# 5_0inch_IPS_for_TerasicDEs.net
KiCad netlist of a schematic drawn in Altium Designer
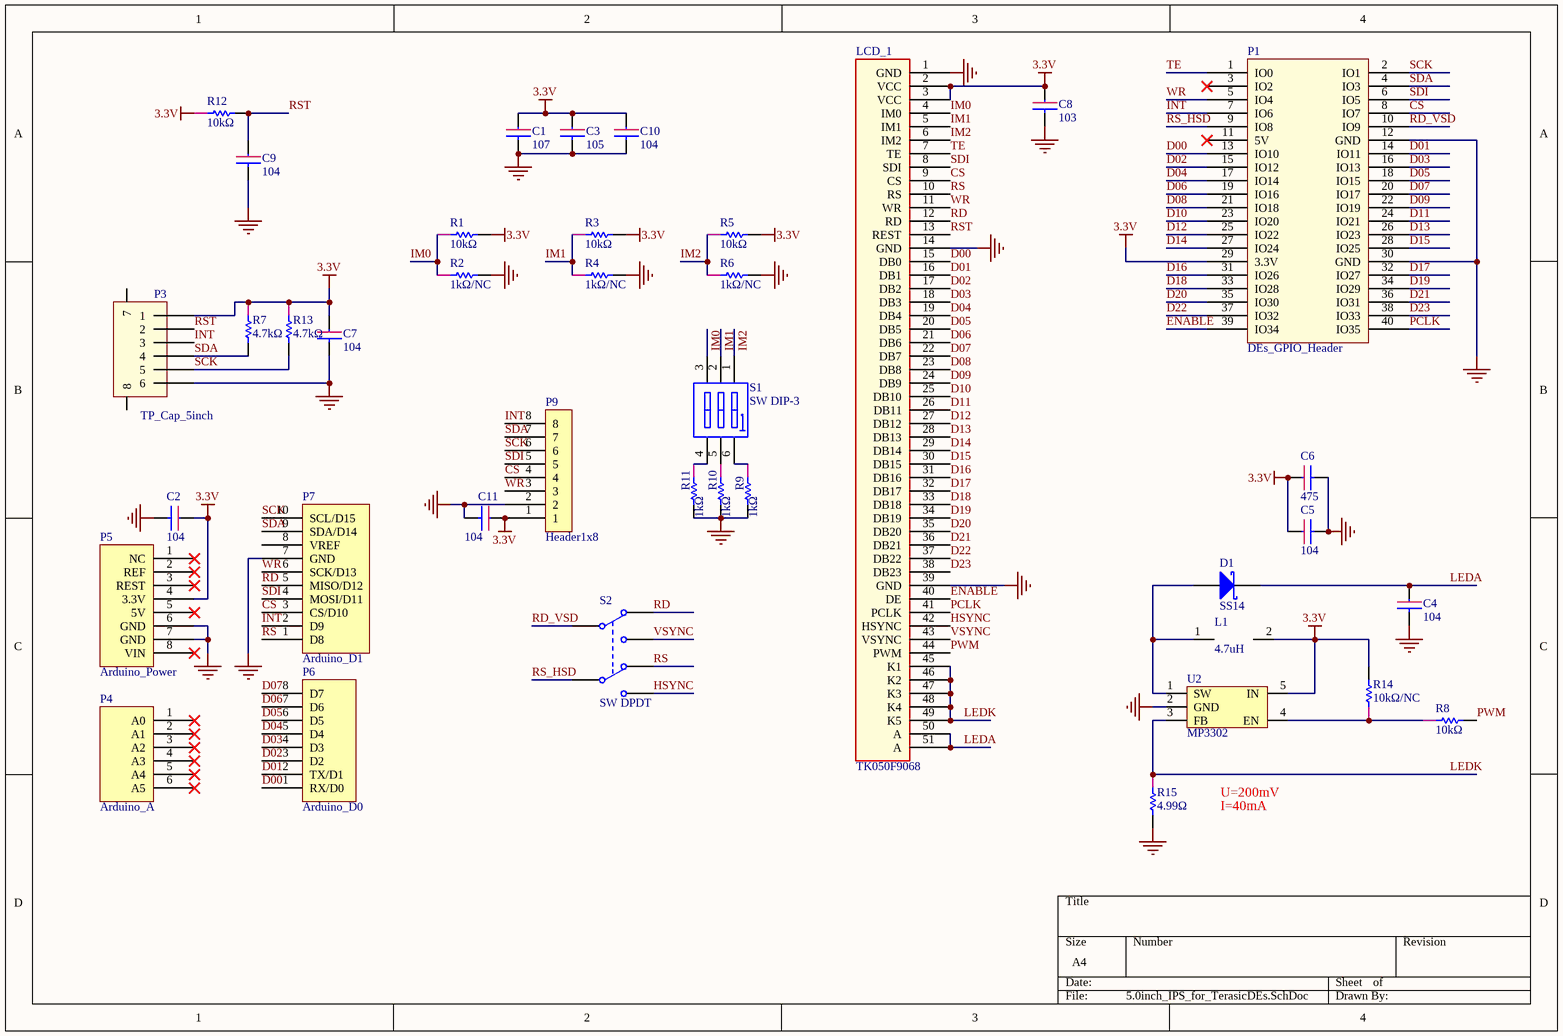
[diagram p0: 5.0inch_IPS_for_TerasicDEs.SchDoc]

(export (version "E")
  (design (tool "Eeschema 10.0.6"))
  (components
    (comp (ref "C1") (value "107") (footprint "C3528B") (libsource (lib "Tiky") (part "cap")))
    (comp (ref "C2") (value "104") (footprint "C0603-2") (libsource (lib "Tiky") (part "cap")))
    (comp (ref "C3") (value "105") (footprint "C3216A") (libsource (lib "Tiky") (part "cap")))
    (comp (ref "C4") (value "104") (footprint "C0603-2") (libsource (lib "Tiky") (part "cap")))
    (comp (ref "C5") (value "104") (footprint "C0603-1") (libsource (lib "Tiky") (part "cap")))
    (comp (ref "C6") (value "475") (footprint "C0603-2") (libsource (lib "Tiky") (part "cap")))
    (comp (ref "C7") (value "104") (footprint "C0603-1") (libsource (lib "Tiky") (part "cap")))
    (comp (ref "C8") (value "103") (footprint "C0603-1") (libsource (lib "Tiky") (part "cap")))
    (comp (ref "C9")
      (value "104")
      (footprint "C0603-2")
      (libsource (lib "5.0inch_IPS_for_TerasicDEs") (part "cap"))
    )
    (comp (ref "C10") (value "104") (footprint "C0603-1") (libsource (lib "Tiky") (part "cap")))
    (comp (ref "C11") (value "104") (footprint "C0603-2") (libsource (lib "Tiky") (part "cap")))
    (comp (ref "D1")
      (value "SS14")
      (footprint "SOD123")
      (description "Schottky Diode")
      (fields (field (name "PUBLISHER") "Altium Limited"))
      (libsource (lib "Miscellaneous Devices") (part "D Schottky"))
    )
    (comp (ref "L1") (value "4.7uH") (footprint "L453226") (libsource (lib "Tiky") (part "Inductor")))
    (comp (ref "LCD_1")
      (value "TK050F9068")
      (footprint "TK050F5590")
      (libsource (lib "Tiky") (part "TK050F9068"))
    )
    (comp (ref "P1")
      (value "DEs_GPIO_Header")
      (footprint "P_HEAD_2X20-n")
      (libsource (lib "5.0inch_IPS_for_TerasicDEs") (part "DEs_GPIO_Header"))
    )
    (comp (ref "P3")
      (value "TP_Cap_5inch")
      (footprint "TP_CAP_5INCH")
      (libsource (lib "Tiky") (part "BHEADSMD1x6"))
    )
    (comp (ref "P4")
      (value "Arduino_A")
      (footprint "SMT_Pin1x6C")
      (libsource (lib "5.0_inch_IPS_TFT_for_Terasic_DE_Boards") (part "Arduino_A"))
    )
    (comp (ref "P5")
      (value "Arduino_Power")
      (footprint "SMT_Pin1x8C")
      (libsource (lib "5.0_inch_IPS_TFT_for_Terasic_DE_Boards") (part "Arduino_Power"))
    )
    (comp (ref "P6")
      (value "Arduino_D0")
      (footprint "SMT_Pin1x8C")
      (libsource (lib "5.0_inch_IPS_TFT_for_Terasic_DE_Boards") (part "Arduino_D0"))
    )
    (comp (ref "P7")
      (value "Arduino_D1")
      (footprint "SMT_Pin1x10C")
      (libsource (lib "5.0_inch_IPS_TFT_for_Terasic_DE_Boards") (part "Arduino_D1"))
    )
    (comp (ref "P9")
      (value "Header1x8")
      (footprint "SMT_Pin1x8")
      (libsource (lib "5.0inch_IPS_for_TerasicDEs") (part "Header1x8"))
    )
    (comp (ref "R1") (value "10kΩ") (footprint "R0603") (libsource (lib "Tiky") (part "Resistor")))
    (comp (ref "R2") (value "1kΩ/NC") (footprint "R0603") (libsource (lib "Tiky") (part "Resistor")))
    (comp (ref "R3") (value "10kΩ") (footprint "R0603") (libsource (lib "Tiky") (part "Resistor")))
    (comp (ref "R4") (value "1kΩ/NC") (footprint "R0603") (libsource (lib "Tiky") (part "Resistor")))
    (comp (ref "R5") (value "10kΩ") (footprint "R0603") (libsource (lib "Tiky") (part "Resistor")))
    (comp (ref "R6") (value "1kΩ/NC") (footprint "R0603") (libsource (lib "Tiky") (part "Resistor")))
    (comp (ref "R7") (value "4.7kΩ") (footprint "R0603") (libsource (lib "Tiky") (part "Resistor")))
    (comp (ref "R8") (value "10kΩ") (footprint "R0603") (libsource (lib "Tiky") (part "Resistor")))
    (comp (ref "R9")
      (value "1kΩ")
      (footprint "R0603")
      (libsource (lib "5.0inch_IPS_for_TerasicDEs") (part "Resistor"))
    )
    (comp (ref "R10")
      (value "1kΩ")
      (footprint "R0603")
      (libsource (lib "5.0inch_IPS_for_TerasicDEs") (part "Resistor"))
    )
    (comp (ref "R11")
      (value "1kΩ")
      (footprint "R0603")
      (libsource (lib "5.0inch_IPS_for_TerasicDEs") (part "Resistor"))
    )
    (comp (ref "R12")
      (value "10kΩ")
      (footprint "R0603")
      (libsource (lib "5.0inch_IPS_for_TerasicDEs") (part "Resistor"))
    )
    (comp (ref "R13")
      (value "4.7kΩ")
      (footprint "R0603")
      (libsource (lib "5.0inch_IPS_for_TerasicDEs") (part "Resistor"))
    )
    (comp (ref "R14") (value "10kΩ/NC") (footprint "R0603") (libsource (lib "Tiky") (part "Resistor")))
    (comp (ref "R15") (value "4.99Ω") (footprint "R0603") (libsource (lib "Tiky") (part "Resistor")))
    (comp (ref "S1")
      (value "SW DIP-3")
      (footprint "DIP3-1.27")
      (description "DIP Switch, 3 Position, SPST")
      (fields (field (name "PUBLISHER") "Altium Limited"))
      (libsource (lib "Miscellaneous Devices") (part "SW DIP-3"))
    )
    (comp (ref "S2")
      (value "SW DPDT")
      (footprint "MSS-22C02")
      (description "Switch")
      (fields (field (name "PUBLISHER") "Altium Limited"))
      (libsource (lib "5.0inch_IPS_for_TerasicDEs") (part "SW DPDT"))
    )
    (comp (ref "U2") (value "MP3302") (footprint "SOT23-5") (libsource (lib "Tiky") (part "MP3302")))
  )
  (nets
    (net (code "1") (name "/CS") (class "Default")
      (node (ref "LCD_1") (pin "9") (pinfunction "CS_9") (pintype "passive"))
      (node (ref "P1") (pin "8") (pinfunction "IO7_8") (pintype "passive"))
      (node (ref "P7") (pin "3") (pinfunction "CS/D10_3") (pintype "passive"))
      (node (ref "P9") (pin "4") (pinfunction "4_4") (pintype "passive"))
    )
    (net (code "2") (name "/D00") (class "Default")
      (node (ref "LCD_1") (pin "15") (pinfunction "DB0_15") (pintype "passive"))
      (node (ref "P1") (pin "13") (pinfunction "IO10_13") (pintype "passive"))
      (node (ref "P6") (pin "1") (pinfunction "RX/D0_1") (pintype "passive"))
    )
    (net (code "3") (name "/D01") (class "Default")
      (node (ref "LCD_1") (pin "16") (pinfunction "DB1_16") (pintype "passive"))
      (node (ref "P1") (pin "14") (pinfunction "IO11_14") (pintype "passive"))
      (node (ref "P6") (pin "2") (pinfunction "TX/D1_2") (pintype "passive"))
    )
    (net (code "4") (name "/D02") (class "Default")
      (node (ref "LCD_1") (pin "17") (pinfunction "DB2_17") (pintype "passive"))
      (node (ref "P1") (pin "15") (pinfunction "IO12_15") (pintype "passive"))
      (node (ref "P6") (pin "3") (pinfunction "D2_3") (pintype "passive"))
    )
    (net (code "5") (name "/D03") (class "Default")
      (node (ref "LCD_1") (pin "18") (pinfunction "DB3_18") (pintype "passive"))
      (node (ref "P1") (pin "16") (pinfunction "IO13_16") (pintype "passive"))
      (node (ref "P6") (pin "4") (pinfunction "D3_4") (pintype "passive"))
    )
    (net (code "6") (name "/D04") (class "Default")
      (node (ref "LCD_1") (pin "19") (pinfunction "DB4_19") (pintype "passive"))
      (node (ref "P1") (pin "17") (pinfunction "IO14_17") (pintype "passive"))
      (node (ref "P6") (pin "5") (pinfunction "D4_5") (pintype "passive"))
    )
    (net (code "7") (name "/D05") (class "Default")
      (node (ref "LCD_1") (pin "20") (pinfunction "DB5_20") (pintype "passive"))
      (node (ref "P1") (pin "18") (pinfunction "IO15_18") (pintype "passive"))
      (node (ref "P6") (pin "6") (pinfunction "D5_6") (pintype "passive"))
    )
    (net (code "8") (name "/D06") (class "Default")
      (node (ref "LCD_1") (pin "21") (pinfunction "DB6_21") (pintype "passive"))
      (node (ref "P1") (pin "19") (pinfunction "IO16_19") (pintype "passive"))
      (node (ref "P6") (pin "7") (pinfunction "D6_7") (pintype "passive"))
    )
    (net (code "9") (name "/D07") (class "Default")
      (node (ref "LCD_1") (pin "22") (pinfunction "DB7_22") (pintype "passive"))
      (node (ref "P1") (pin "20") (pinfunction "IO17_20") (pintype "passive"))
      (node (ref "P6") (pin "8") (pinfunction "D7_8") (pintype "passive"))
    )
    (net (code "10") (name "/D08") (class "Default")
      (node (ref "LCD_1") (pin "23") (pinfunction "DB8_23") (pintype "passive"))
      (node (ref "P1") (pin "21") (pinfunction "IO18_21") (pintype "passive"))
    )
    (net (code "11") (name "/D09") (class "Default")
      (node (ref "LCD_1") (pin "24") (pinfunction "DB9_24") (pintype "passive"))
      (node (ref "P1") (pin "22") (pinfunction "IO19_22") (pintype "passive"))
    )
    (net (code "12") (name "/D10") (class "Default")
      (node (ref "LCD_1") (pin "25") (pinfunction "DB10_25") (pintype "passive"))
      (node (ref "P1") (pin "23") (pinfunction "IO20_23") (pintype "passive"))
    )
    (net (code "13") (name "/D11") (class "Default")
      (node (ref "LCD_1") (pin "26") (pinfunction "DB11_26") (pintype "passive"))
      (node (ref "P1") (pin "24") (pinfunction "IO21_24") (pintype "passive"))
    )
    (net (code "14") (name "/D12") (class "Default")
      (node (ref "LCD_1") (pin "27") (pinfunction "DB12_27") (pintype "passive"))
      (node (ref "P1") (pin "25") (pinfunction "IO22_25") (pintype "passive"))
    )
    (net (code "15") (name "/D13") (class "Default")
      (node (ref "LCD_1") (pin "28") (pinfunction "DB13_28") (pintype "passive"))
      (node (ref "P1") (pin "26") (pinfunction "IO23_26") (pintype "passive"))
    )
    (net (code "16") (name "/D14") (class "Default")
      (node (ref "LCD_1") (pin "29") (pinfunction "DB14_29") (pintype "passive"))
      (node (ref "P1") (pin "27") (pinfunction "IO24_27") (pintype "passive"))
    )
    (net (code "17") (name "/D15") (class "Default")
      (node (ref "LCD_1") (pin "30") (pinfunction "DB15_30") (pintype "passive"))
      (node (ref "P1") (pin "28") (pinfunction "IO25_28") (pintype "passive"))
    )
    (net (code "18") (name "/D16") (class "Default")
      (node (ref "LCD_1") (pin "31") (pinfunction "DB16_31") (pintype "passive"))
      (node (ref "P1") (pin "31") (pinfunction "IO26_31") (pintype "passive"))
    )
    (net (code "19") (name "/D17") (class "Default")
      (node (ref "LCD_1") (pin "32") (pinfunction "DB17_32") (pintype "passive"))
      (node (ref "P1") (pin "32") (pinfunction "IO27_32") (pintype "passive"))
    )
    (net (code "20") (name "/D18") (class "Default")
      (node (ref "LCD_1") (pin "33") (pinfunction "DB18_33") (pintype "passive"))
      (node (ref "P1") (pin "33") (pinfunction "IO28_33") (pintype "passive"))
    )
    (net (code "21") (name "/D19") (class "Default")
      (node (ref "LCD_1") (pin "34") (pinfunction "DB19_34") (pintype "passive"))
      (node (ref "P1") (pin "34") (pinfunction "IO29_34") (pintype "passive"))
    )
    (net (code "22") (name "/D20") (class "Default")
      (node (ref "LCD_1") (pin "35") (pinfunction "DB20_35") (pintype "passive"))
      (node (ref "P1") (pin "35") (pinfunction "IO30_35") (pintype "passive"))
    )
    (net (code "23") (name "/D21") (class "Default")
      (node (ref "LCD_1") (pin "36") (pinfunction "DB21_36") (pintype "passive"))
      (node (ref "P1") (pin "36") (pinfunction "IO31_36") (pintype "passive"))
    )
    (net (code "24") (name "/D22") (class "Default")
      (node (ref "LCD_1") (pin "37") (pinfunction "DB22_37") (pintype "passive"))
      (node (ref "P1") (pin "37") (pinfunction "IO32_37") (pintype "passive"))
    )
    (net (code "25") (name "/D23") (class "Default")
      (node (ref "LCD_1") (pin "38") (pinfunction "DB23_38") (pintype "passive"))
      (node (ref "P1") (pin "38") (pinfunction "IO33_38") (pintype "passive"))
    )
    (net (code "26") (name "/ENABLE") (class "Default")
      (node (ref "LCD_1") (pin "40") (pinfunction "DE_40") (pintype "passive"))
      (node (ref "P1") (pin "39") (pinfunction "IO34_39") (pintype "passive"))
    )
    (net (code "27") (name "/HSYNC") (class "Default")
      (node (ref "LCD_1") (pin "42") (pinfunction "HSYNC_42") (pintype "passive"))
      (node (ref "S2") (pin "4") (pinfunction "NO2_4") (pintype "passive"))
    )
    (net (code "28") (name "/IM0") (class "Default")
      (node (ref "LCD_1") (pin "4") (pinfunction "IM0_4") (pintype "passive"))
      (node (ref "R1") (pin "1") (pinfunction "1_1") (pintype "passive"))
      (node (ref "R2") (pin "1") (pinfunction "1_1") (pintype "passive"))
      (node (ref "S1") (pin "3") (pinfunction "A3_3") (pintype "passive"))
    )
    (net (code "29") (name "/IM1") (class "Default")
      (node (ref "LCD_1") (pin "5") (pinfunction "IM1_5") (pintype "passive"))
      (node (ref "R3") (pin "1") (pinfunction "1_1") (pintype "passive"))
      (node (ref "R4") (pin "1") (pinfunction "1_1") (pintype "passive"))
      (node (ref "S1") (pin "2") (pinfunction "A2_2") (pintype "passive"))
    )
    (net (code "30") (name "/IM2") (class "Default")
      (node (ref "LCD_1") (pin "6") (pinfunction "IM2_6") (pintype "passive"))
      (node (ref "R5") (pin "1") (pinfunction "1_1") (pintype "passive"))
      (node (ref "R6") (pin "1") (pinfunction "1_1") (pintype "passive"))
      (node (ref "S1") (pin "1") (pinfunction "A1_1") (pintype "passive"))
    )
    (net (code "31") (name "/INT") (class "Default")
      (node (ref "P1") (pin "7") (pinfunction "IO6_7") (pintype "passive"))
      (node (ref "P3") (pin "3") (pinfunction "3_3") (pintype "passive"))
      (node (ref "P7") (pin "2") (pinfunction "D9_2") (pintype "passive"))
      (node (ref "P9") (pin "8") (pinfunction "8_8") (pintype "passive"))
    )
    (net (code "32") (name "/LEDA") (class "Default")
      (node (ref "C4") (pin "1") (pinfunction "1_1") (pintype "passive"))
      (node (ref "D1") (pin "2") (pinfunction "K_2") (pintype "passive"))
      (node (ref "LCD_1") (pin "50") (pinfunction "A_50") (pintype "passive"))
      (node (ref "LCD_1") (pin "51") (pinfunction "A_51") (pintype "passive"))
    )
    (net (code "33") (name "/LEDK") (class "Default")
      (node (ref "LCD_1") (pin "45") (pinfunction "K1_45") (pintype "passive"))
      (node (ref "LCD_1") (pin "46") (pinfunction "K2_46") (pintype "passive"))
      (node (ref "LCD_1") (pin "47") (pinfunction "K3_47") (pintype "passive"))
      (node (ref "LCD_1") (pin "48") (pinfunction "K4_48") (pintype "passive"))
      (node (ref "LCD_1") (pin "49") (pinfunction "K5_49") (pintype "passive"))
      (node (ref "R15") (pin "1") (pinfunction "1_1") (pintype "passive"))
      (node (ref "U2") (pin "3") (pinfunction "FB_3") (pintype "passive"))
    )
    (net (code "34") (name "/PCLK") (class "Default")
      (node (ref "LCD_1") (pin "41") (pinfunction "PCLK_41") (pintype "passive"))
      (node (ref "P1") (pin "40") (pinfunction "IO35_40") (pintype "passive"))
    )
    (net (code "35") (name "/PWM") (class "Default")
      (node (ref "LCD_1") (pin "44") (pinfunction "PWM_44") (pintype "passive"))
      (node (ref "R8") (pin "2") (pinfunction "2_2") (pintype "passive"))
    )
    (net (code "36") (name "/RD") (class "Default")
      (node (ref "LCD_1") (pin "12") (pinfunction "RD_12") (pintype "passive"))
      (node (ref "P7") (pin "5") (pinfunction "MISO/D12_5") (pintype "passive"))
      (node (ref "S2") (pin "1") (pinfunction "NC1_1") (pintype "passive"))
    )
    (net (code "37") (name "/RD_VSD") (class "Default")
      (node (ref "P1") (pin "10") (pinfunction "IO9_10") (pintype "passive"))
      (node (ref "S2") (pin "2") (pinfunction "COMMON1_2") (pintype "passive"))
    )
    (net (code "38") (name "/RS") (class "Default")
      (node (ref "LCD_1") (pin "10") (pinfunction "RS_10") (pintype "passive"))
      (node (ref "P7") (pin "1") (pinfunction "D8_1") (pintype "passive"))
      (node (ref "S2") (pin "6") (pinfunction "NC2_6") (pintype "passive"))
    )
    (net (code "39") (name "/RST") (class "Default")
      (node (ref "C9") (pin "1") (pinfunction "1_1") (pintype "passive"))
      (node (ref "LCD_1") (pin "13") (pinfunction "REST_13") (pintype "passive"))
      (node (ref "P3") (pin "2") (pinfunction "2_2") (pintype "passive"))
      (node (ref "R12") (pin "2") (pinfunction "2_2") (pintype "passive"))
    )
    (net (code "40") (name "/RS_HSD") (class "Default")
      (node (ref "P1") (pin "9") (pinfunction "IO8_9") (pintype "passive"))
      (node (ref "S2") (pin "5") (pinfunction "COMMON2_5") (pintype "passive"))
    )
    (net (code "41") (name "/SCK") (class "Default")
      (node (ref "P1") (pin "2") (pinfunction "IO1_2") (pintype "passive"))
      (node (ref "P3") (pin "5") (pinfunction "5_5") (pintype "passive"))
      (node (ref "P7") (pin "10") (pinfunction "SCL/D15_10") (pintype "passive"))
      (node (ref "P9") (pin "6") (pinfunction "6_6") (pintype "passive"))
      (node (ref "R13") (pin "2") (pinfunction "2_2") (pintype "passive"))
    )
    (net (code "42") (name "/SDA") (class "Default")
      (node (ref "P1") (pin "4") (pinfunction "IO3_4") (pintype "passive"))
      (node (ref "P3") (pin "4") (pinfunction "4_4") (pintype "passive"))
      (node (ref "P7") (pin "9") (pinfunction "SDA/D14_9") (pintype "passive"))
      (node (ref "P9") (pin "7") (pinfunction "7_7") (pintype "passive"))
      (node (ref "R7") (pin "2") (pinfunction "2_2") (pintype "passive"))
    )
    (net (code "43") (name "/SDI") (class "Default")
      (node (ref "LCD_1") (pin "8") (pinfunction "SDI_8") (pintype "passive"))
      (node (ref "P1") (pin "6") (pinfunction "IO5_6") (pintype "passive"))
      (node (ref "P7") (pin "4") (pinfunction "MOSI/D11_4") (pintype "passive"))
      (node (ref "P9") (pin "5") (pinfunction "5_5") (pintype "passive"))
    )
    (net (code "44") (name "/TE") (class "Default")
      (node (ref "LCD_1") (pin "7") (pinfunction "TE_7") (pintype "passive"))
      (node (ref "P1") (pin "1") (pinfunction "IO0_1") (pintype "passive"))
    )
    (net (code "45") (name "/VSYNC") (class "Default")
      (node (ref "LCD_1") (pin "43") (pinfunction "VSYNC_43") (pintype "passive"))
      (node (ref "S2") (pin "3") (pinfunction "NO1_3") (pintype "passive"))
    )
    (net (code "46") (name "/WR") (class "Default")
      (node (ref "LCD_1") (pin "11") (pinfunction "WR_11") (pintype "passive"))
      (node (ref "P1") (pin "5") (pinfunction "IO4_5") (pintype "passive"))
      (node (ref "P7") (pin "6") (pinfunction "SCK/D13_6") (pintype "passive"))
      (node (ref "P9") (pin "3") (pinfunction "3_3") (pintype "passive"))
    )
    (net (code "47") (name "3.3V") (class "Default")
      (node (ref "C1") (pin "1") (pinfunction "1_1") (pintype "passive"))
      (node (ref "C10") (pin "1") (pinfunction "1_1") (pintype "passive"))
      (node (ref "C11") (pin "1") (pinfunction "1_1") (pintype "passive"))
      (node (ref "C2") (pin "1") (pinfunction "1_1") (pintype "passive"))
      (node (ref "C3") (pin "1") (pinfunction "1_1") (pintype "passive"))
      (node (ref "C5") (pin "1") (pinfunction "1_1") (pintype "passive"))
      (node (ref "C6") (pin "1") (pinfunction "1_1") (pintype "passive"))
      (node (ref "C7") (pin "1") (pinfunction "1_1") (pintype "passive"))
      (node (ref "C8") (pin "1") (pinfunction "1_1") (pintype "passive"))
      (node (ref "L1") (pin "2") (pinfunction "2_2") (pintype "passive"))
      (node (ref "LCD_1") (pin "2") (pinfunction "VCC_2") (pintype "passive"))
      (node (ref "LCD_1") (pin "3") (pinfunction "VCC_3") (pintype "passive"))
      (node (ref "P1") (pin "29") (pinfunction "3.3V_29") (pintype "passive"))
      (node (ref "P3") (pin "1") (pinfunction "1_1") (pintype "passive"))
      (node (ref "P5") (pin "4") (pinfunction "3.3V_4") (pintype "passive"))
      (node (ref "P9") (pin "1") (pinfunction "1_1") (pintype "passive"))
      (node (ref "R1") (pin "2") (pinfunction "2_2") (pintype "passive"))
      (node (ref "R12") (pin "1") (pinfunction "1_1") (pintype "passive"))
      (node (ref "R13") (pin "1") (pinfunction "1_1") (pintype "passive"))
      (node (ref "R14") (pin "2") (pinfunction "2_2") (pintype "passive"))
      (node (ref "R3") (pin "2") (pinfunction "2_2") (pintype "passive"))
      (node (ref "R5") (pin "2") (pinfunction "2_2") (pintype "passive"))
      (node (ref "R7") (pin "1") (pinfunction "1_1") (pintype "passive"))
      (node (ref "U2") (pin "5") (pinfunction "IN_5") (pintype "passive"))
    )
    (net (code "48") (name "GND") (class "Default")
      (node (ref "C1") (pin "2") (pinfunction "2_2") (pintype "passive"))
      (node (ref "C10") (pin "2") (pinfunction "2_2") (pintype "passive"))
      (node (ref "C11") (pin "2") (pinfunction "2_2") (pintype "passive"))
      (node (ref "C2") (pin "2") (pinfunction "2_2") (pintype "passive"))
      (node (ref "C3") (pin "2") (pinfunction "2_2") (pintype "passive"))
      (node (ref "C4") (pin "2") (pinfunction "2_2") (pintype "passive"))
      (node (ref "C5") (pin "2") (pinfunction "2_2") (pintype "passive"))
      (node (ref "C6") (pin "2") (pinfunction "2_2") (pintype "passive"))
      (node (ref "C7") (pin "2") (pinfunction "2_2") (pintype "passive"))
      (node (ref "C8") (pin "2") (pinfunction "2_2") (pintype "passive"))
      (node (ref "C9") (pin "2") (pinfunction "2_2") (pintype "passive"))
      (node (ref "LCD_1") (pin "1") (pinfunction "GND_1") (pintype "passive"))
      (node (ref "LCD_1") (pin "14") (pinfunction "GND_14") (pintype "passive"))
      (node (ref "LCD_1") (pin "39") (pinfunction "GND_39") (pintype "passive"))
      (node (ref "P1") (pin "12") (pinfunction "GND_12") (pintype "passive"))
      (node (ref "P1") (pin "30") (pinfunction "GND_30") (pintype "passive"))
      (node (ref "P3") (pin "6") (pinfunction "6_6") (pintype "passive"))
      (node (ref "P5") (pin "6") (pinfunction "GND_6") (pintype "passive"))
      (node (ref "P5") (pin "7") (pinfunction "GND_7") (pintype "passive"))
      (node (ref "P7") (pin "7") (pinfunction "GND_7") (pintype "passive"))
      (node (ref "P9") (pin "2") (pinfunction "2_2") (pintype "passive"))
      (node (ref "R10") (pin "2") (pinfunction "2_2") (pintype "passive"))
      (node (ref "R11") (pin "2") (pinfunction "2_2") (pintype "passive"))
      (node (ref "R15") (pin "2") (pinfunction "2_2") (pintype "passive"))
      (node (ref "R2") (pin "2") (pinfunction "2_2") (pintype "passive"))
      (node (ref "R4") (pin "2") (pinfunction "2_2") (pintype "passive"))
      (node (ref "R6") (pin "2") (pinfunction "2_2") (pintype "passive"))
      (node (ref "R9") (pin "2") (pinfunction "2_2") (pintype "passive"))
      (node (ref "U2") (pin "2") (pinfunction "GND_2") (pintype "passive"))
    )
    (net (code "49") (name "Net-(D1-A)") (class "Default")
      (node (ref "D1") (pin "1") (pinfunction "A_1") (pintype "passive"))
      (node (ref "L1") (pin "1") (pinfunction "1_1") (pintype "passive"))
      (node (ref "U2") (pin "1") (pinfunction "SW_1") (pintype "passive"))
    )
    (net (code "50") (name "Net-(S1-B1)") (class "Default")
      (node (ref "R9") (pin "1") (pinfunction "1_1") (pintype "passive"))
      (node (ref "S1") (pin "6") (pinfunction "B1_6") (pintype "passive"))
    )
    (net (code "51") (name "Net-(S1-B2)") (class "Default")
      (node (ref "R10") (pin "1") (pinfunction "1_1") (pintype "passive"))
      (node (ref "S1") (pin "5") (pinfunction "B2_5") (pintype "passive"))
    )
    (net (code "52") (name "Net-(S1-B3)") (class "Default")
      (node (ref "R11") (pin "1") (pinfunction "1_1") (pintype "passive"))
      (node (ref "S1") (pin "4") (pinfunction "B3_4") (pintype "passive"))
    )
    (net (code "53") (name "Net-(U2-EN)") (class "Default")
      (node (ref "R14") (pin "1") (pinfunction "1_1") (pintype "passive"))
      (node (ref "R8") (pin "1") (pinfunction "1_1") (pintype "passive"))
      (node (ref "U2") (pin "4") (pinfunction "EN_4") (pintype "passive"))
    )
    (net (code "54") (name "unconnected-(P1-5V-Pad11)") (class "Default")
      (node (ref "P1") (pin "11") (pinfunction "5V_11") (pintype "passive+no_connect"))
    )
    (net (code "55") (name "unconnected-(P1-IO2-Pad3)") (class "Default")
      (node (ref "P1") (pin "3") (pinfunction "IO2_3") (pintype "passive+no_connect"))
    )
    (net (code "56") (name "unconnected-(P3-Pad7)") (class "Default")
      (node (ref "P3") (pin "7") (pinfunction "7_7") (pintype "passive"))
    )
    (net (code "57") (name "unconnected-(P3-Pad8)") (class "Default")
      (node (ref "P3") (pin "8") (pinfunction "8_8") (pintype "passive"))
    )
    (net (code "58") (name "unconnected-(P4-A0-Pad1)") (class "Default")
      (node (ref "P4") (pin "1") (pinfunction "A0_1") (pintype "passive+no_connect"))
    )
    (net (code "59") (name "unconnected-(P4-A1-Pad2)") (class "Default")
      (node (ref "P4") (pin "2") (pinfunction "A1_2") (pintype "passive+no_connect"))
    )
    (net (code "60") (name "unconnected-(P4-A2-Pad3)") (class "Default")
      (node (ref "P4") (pin "3") (pinfunction "A2_3") (pintype "passive+no_connect"))
    )
    (net (code "61") (name "unconnected-(P4-A3-Pad4)") (class "Default")
      (node (ref "P4") (pin "4") (pinfunction "A3_4") (pintype "passive+no_connect"))
    )
    (net (code "62") (name "unconnected-(P4-A4-Pad5)") (class "Default")
      (node (ref "P4") (pin "5") (pinfunction "A4_5") (pintype "passive+no_connect"))
    )
    (net (code "63") (name "unconnected-(P4-A5-Pad6)") (class "Default")
      (node (ref "P4") (pin "6") (pinfunction "A5_6") (pintype "passive+no_connect"))
    )
    (net (code "64") (name "unconnected-(P5-5V-Pad5)") (class "Default")
      (node (ref "P5") (pin "5") (pinfunction "5V_5") (pintype "passive+no_connect"))
    )
    (net (code "65") (name "unconnected-(P5-NC-Pad1)") (class "Default")
      (node (ref "P5") (pin "1") (pinfunction "NC_1") (pintype "passive+no_connect"))
    )
    (net (code "66") (name "unconnected-(P5-REF-Pad2)") (class "Default")
      (node (ref "P5") (pin "2") (pinfunction "REF_2") (pintype "passive+no_connect"))
    )
    (net (code "67") (name "unconnected-(P5-REST-Pad3)") (class "Default")
      (node (ref "P5") (pin "3") (pinfunction "REST_3") (pintype "passive+no_connect"))
    )
    (net (code "68") (name "unconnected-(P5-VIN-Pad8)") (class "Default")
      (node (ref "P5") (pin "8") (pinfunction "VIN_8") (pintype "passive+no_connect"))
    )
    (net (code "69") (name "unconnected-(P7-VREF-Pad8)") (class "Default")
      (node (ref "P7") (pin "8") (pinfunction "VREF_8") (pintype "passive"))
    )
  )
)
